# TMP117_Temperature_Sensors.net
KiCad netlist of a schematic drawn in Altium Designer
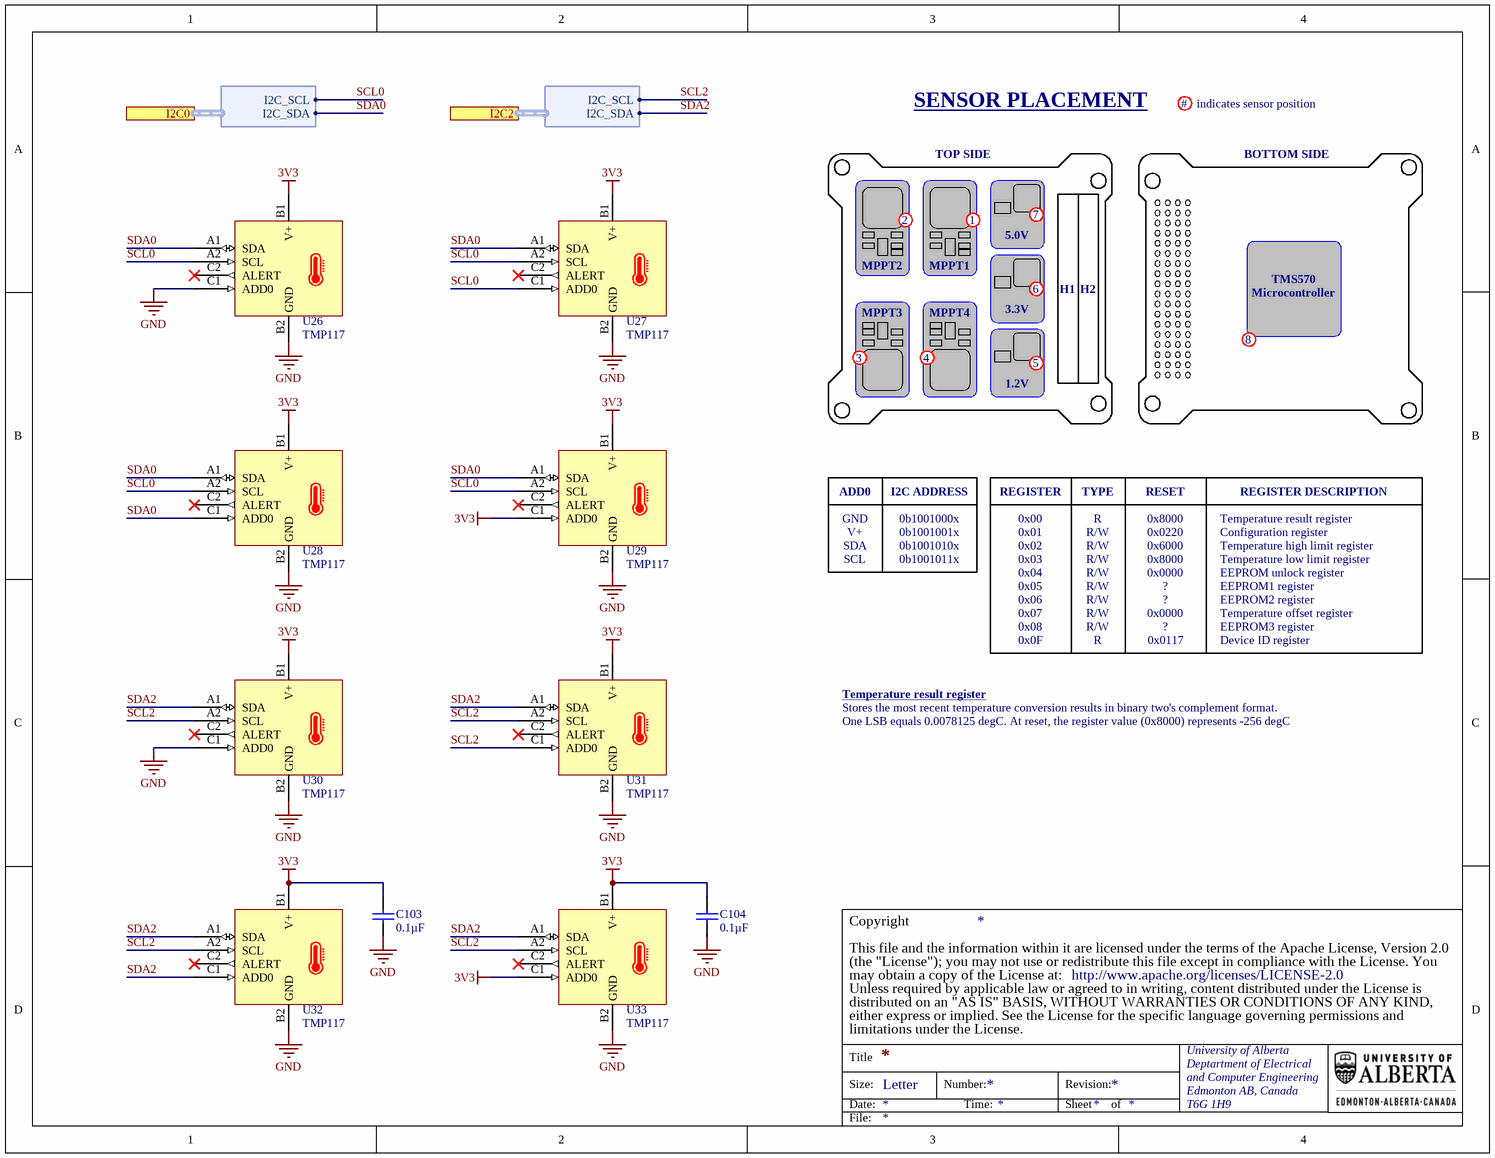
[diagram p0: TMP117 Temperature Sensors.SchDoc]

(export (version "E")
  (design (tool "Eeschema 10.0.6"))
  (components
    (comp (ref "C103")
      (value "0.1µF")
      (footprint "TDK-CGA2B")
      (description "CAP CER 0.1UF 50V X7R 0402")
      (fields
        (field (name "PART NUMBER") "PC-TDK-02259")
        (field (name "MANUFACTURER PART NUMBER") "CGA2B3X7R1H104K050BB")
        (field (name "PUBLISHER") "AlbertaSat")
      )
      (libsource (lib "Database") (part "Cap"))
    )
    (comp (ref "C104")
      (value "0.1µF")
      (footprint "TDK-CGA2B")
      (description "CAP CER 0.1UF 50V X7R 0402")
      (fields
        (field (name "PART NUMBER") "PC-TDK-02259")
        (field (name "MANUFACTURER PART NUMBER") "CGA2B3X7R1H104K050BB")
        (field (name "PUBLISHER") "AlbertaSat")
      )
      (libsource (lib "Database") (part "Cap"))
    )
    (comp (ref "U26")
      (value "TMP117")
      (footprint "TI-YBG0006-C01")
      (description "Temperature Sensor Digital, Local -55°C ~ 150°C 16 b 6-DSBGA (1.49x0.95)")
      (fields (field (name "PART NUMBER") "164") (field (name "MANUFACTURER PART NUMBER") "TMP117NAIYBGR"))
      (libsource (lib "Database") (part "TMP117NAIYBGR"))
    )
    (comp (ref "U27")
      (value "TMP117")
      (footprint "TI-YBG0006-C01")
      (description "Temperature Sensor Digital, Local -55°C ~ 150°C 16 b 6-DSBGA (1.49x0.95)")
      (fields (field (name "PART NUMBER") "164") (field (name "MANUFACTURER PART NUMBER") "TMP117NAIYBGR"))
      (libsource (lib "Database") (part "TMP117NAIYBGR"))
    )
    (comp (ref "U28")
      (value "TMP117")
      (footprint "TI-YBG0006-C01")
      (description "Temperature Sensor Digital, Local -55°C ~ 150°C 16 b 6-DSBGA (1.49x0.95)")
      (fields (field (name "PART NUMBER") "164") (field (name "MANUFACTURER PART NUMBER") "TMP117NAIYBGR"))
      (libsource (lib "Database") (part "TMP117NAIYBGR"))
    )
    (comp (ref "U29")
      (value "TMP117")
      (footprint "TI-YBG0006-C01")
      (description "Temperature Sensor Digital, Local -55°C ~ 150°C 16 b 6-DSBGA (1.49x0.95)")
      (fields (field (name "PART NUMBER") "164") (field (name "MANUFACTURER PART NUMBER") "TMP117NAIYBGR"))
      (libsource (lib "Database") (part "TMP117NAIYBGR"))
    )
    (comp (ref "U30")
      (value "TMP117")
      (footprint "TI-YBG0006-C01")
      (description "Temperature Sensor Digital, Local -55°C ~ 150°C 16 b 6-DSBGA (1.49x0.95)")
      (fields (field (name "PART NUMBER") "164") (field (name "MANUFACTURER PART NUMBER") "TMP117NAIYBGR"))
      (libsource (lib "Database") (part "TMP117NAIYBGR"))
    )
    (comp (ref "U31")
      (value "TMP117")
      (footprint "TI-YBG0006-C01")
      (description "Temperature Sensor Digital, Local -55°C ~ 150°C 16 b 6-DSBGA (1.49x0.95)")
      (fields (field (name "PART NUMBER") "164") (field (name "MANUFACTURER PART NUMBER") "TMP117NAIYBGR"))
      (libsource (lib "Database") (part "TMP117NAIYBGR"))
    )
    (comp (ref "U32")
      (value "TMP117")
      (footprint "TI-YBG0006-C01")
      (description "Temperature Sensor Digital, Local -55°C ~ 150°C 16 b 6-DSBGA (1.49x0.95)")
      (fields (field (name "PART NUMBER") "164") (field (name "MANUFACTURER PART NUMBER") "TMP117NAIYBGR"))
      (libsource (lib "Database") (part "TMP117NAIYBGR"))
    )
    (comp (ref "U33")
      (value "TMP117")
      (footprint "TI-YBG0006-C01")
      (description "Temperature Sensor Digital, Local -55°C ~ 150°C 16 b 6-DSBGA (1.49x0.95)")
      (fields (field (name "PART NUMBER") "164") (field (name "MANUFACTURER PART NUMBER") "TMP117NAIYBGR"))
      (libsource (lib "Database") (part "TMP117NAIYBGR"))
    )
  )
  (nets
    (net (code "2") (name "/SCL0") (class "Default")
      (node (ref "U26") (pin "A2") (pinfunction "SCL_A2") (pintype "input"))
      (node (ref "U27") (pin "A2") (pinfunction "SCL_A2") (pintype "input"))
      (node (ref "U27") (pin "C1") (pinfunction "ADD0_C1") (pintype "input"))
      (node (ref "U28") (pin "A2") (pinfunction "SCL_A2") (pintype "input"))
      (node (ref "U29") (pin "A2") (pinfunction "SCL_A2") (pintype "input"))
    )
    (net (code "3") (name "/SCL2") (class "Default")
      (node (ref "U30") (pin "A2") (pinfunction "SCL_A2") (pintype "input"))
      (node (ref "U31") (pin "A2") (pinfunction "SCL_A2") (pintype "input"))
      (node (ref "U31") (pin "C1") (pinfunction "ADD0_C1") (pintype "input"))
      (node (ref "U32") (pin "A2") (pinfunction "SCL_A2") (pintype "input"))
      (node (ref "U33") (pin "A2") (pinfunction "SCL_A2") (pintype "input"))
    )
    (net (code "4") (name "/SDA0") (class "Default")
      (node (ref "U26") (pin "A1") (pinfunction "SDA_A1") (pintype "bidirectional"))
      (node (ref "U27") (pin "A1") (pinfunction "SDA_A1") (pintype "bidirectional"))
      (node (ref "U28") (pin "A1") (pinfunction "SDA_A1") (pintype "bidirectional"))
      (node (ref "U28") (pin "C1") (pinfunction "ADD0_C1") (pintype "input"))
      (node (ref "U29") (pin "A1") (pinfunction "SDA_A1") (pintype "bidirectional"))
    )
    (net (code "5") (name "/SDA2") (class "Default")
      (node (ref "U30") (pin "A1") (pinfunction "SDA_A1") (pintype "bidirectional"))
      (node (ref "U31") (pin "A1") (pinfunction "SDA_A1") (pintype "bidirectional"))
      (node (ref "U32") (pin "A1") (pinfunction "SDA_A1") (pintype "bidirectional"))
      (node (ref "U32") (pin "C1") (pinfunction "ADD0_C1") (pintype "input"))
      (node (ref "U33") (pin "A1") (pinfunction "SDA_A1") (pintype "bidirectional"))
    )
    (net (code "7") (name "3V3") (class "Default")
      (node (ref "C103") (pin "1") (pinfunction "1_1") (pintype "passive"))
      (node (ref "C104") (pin "1") (pinfunction "1_1") (pintype "passive"))
      (node (ref "U26") (pin "B1") (pinfunction "V+_B1") (pintype "power_in"))
      (node (ref "U27") (pin "B1") (pinfunction "V+_B1") (pintype "power_in"))
      (node (ref "U28") (pin "B1") (pinfunction "V+_B1") (pintype "power_in"))
      (node (ref "U29") (pin "B1") (pinfunction "V+_B1") (pintype "power_in"))
      (node (ref "U29") (pin "C1") (pinfunction "ADD0_C1") (pintype "input"))
      (node (ref "U30") (pin "B1") (pinfunction "V+_B1") (pintype "power_in"))
      (node (ref "U31") (pin "B1") (pinfunction "V+_B1") (pintype "power_in"))
      (node (ref "U32") (pin "B1") (pinfunction "V+_B1") (pintype "power_in"))
      (node (ref "U33") (pin "B1") (pinfunction "V+_B1") (pintype "power_in"))
      (node (ref "U33") (pin "C1") (pinfunction "ADD0_C1") (pintype "input"))
    )
    (net (code "8") (name "GND") (class "Default")
      (node (ref "C103") (pin "2") (pinfunction "2_2") (pintype "passive"))
      (node (ref "C104") (pin "2") (pinfunction "2_2") (pintype "passive"))
      (node (ref "U26") (pin "B2") (pinfunction "GND_B2") (pintype "power_in"))
      (node (ref "U26") (pin "C1") (pinfunction "ADD0_C1") (pintype "input"))
      (node (ref "U27") (pin "B2") (pinfunction "GND_B2") (pintype "power_in"))
      (node (ref "U28") (pin "B2") (pinfunction "GND_B2") (pintype "power_in"))
      (node (ref "U29") (pin "B2") (pinfunction "GND_B2") (pintype "power_in"))
      (node (ref "U30") (pin "B2") (pinfunction "GND_B2") (pintype "power_in"))
      (node (ref "U30") (pin "C1") (pinfunction "ADD0_C1") (pintype "input"))
      (node (ref "U31") (pin "B2") (pinfunction "GND_B2") (pintype "power_in"))
      (node (ref "U32") (pin "B2") (pinfunction "GND_B2") (pintype "power_in"))
      (node (ref "U33") (pin "B2") (pinfunction "GND_B2") (pintype "power_in"))
    )
    (net (code "9") (name "unconnected-(U26-ALERT-PadC2)") (class "Default")
      (node (ref "U26") (pin "C2") (pinfunction "ALERT_C2") (pintype "output+no_connect"))
    )
    (net (code "10") (name "unconnected-(U27-ALERT-PadC2)") (class "Default")
      (node (ref "U27") (pin "C2") (pinfunction "ALERT_C2") (pintype "output+no_connect"))
    )
    (net (code "11") (name "unconnected-(U28-ALERT-PadC2)") (class "Default")
      (node (ref "U28") (pin "C2") (pinfunction "ALERT_C2") (pintype "output+no_connect"))
    )
    (net (code "12") (name "unconnected-(U29-ALERT-PadC2)") (class "Default")
      (node (ref "U29") (pin "C2") (pinfunction "ALERT_C2") (pintype "output+no_connect"))
    )
    (net (code "13") (name "unconnected-(U30-ALERT-PadC2)") (class "Default")
      (node (ref "U30") (pin "C2") (pinfunction "ALERT_C2") (pintype "output+no_connect"))
    )
    (net (code "14") (name "unconnected-(U31-ALERT-PadC2)") (class "Default")
      (node (ref "U31") (pin "C2") (pinfunction "ALERT_C2") (pintype "output+no_connect"))
    )
    (net (code "15") (name "unconnected-(U32-ALERT-PadC2)") (class "Default")
      (node (ref "U32") (pin "C2") (pinfunction "ALERT_C2") (pintype "output+no_connect"))
    )
    (net (code "16") (name "unconnected-(U33-ALERT-PadC2)") (class "Default")
      (node (ref "U33") (pin "C2") (pinfunction "ALERT_C2") (pintype "output+no_connect"))
    )
  )
)
